# wireless_thermometer.net
KiCad netlist of a schematic drawn in EAGLE
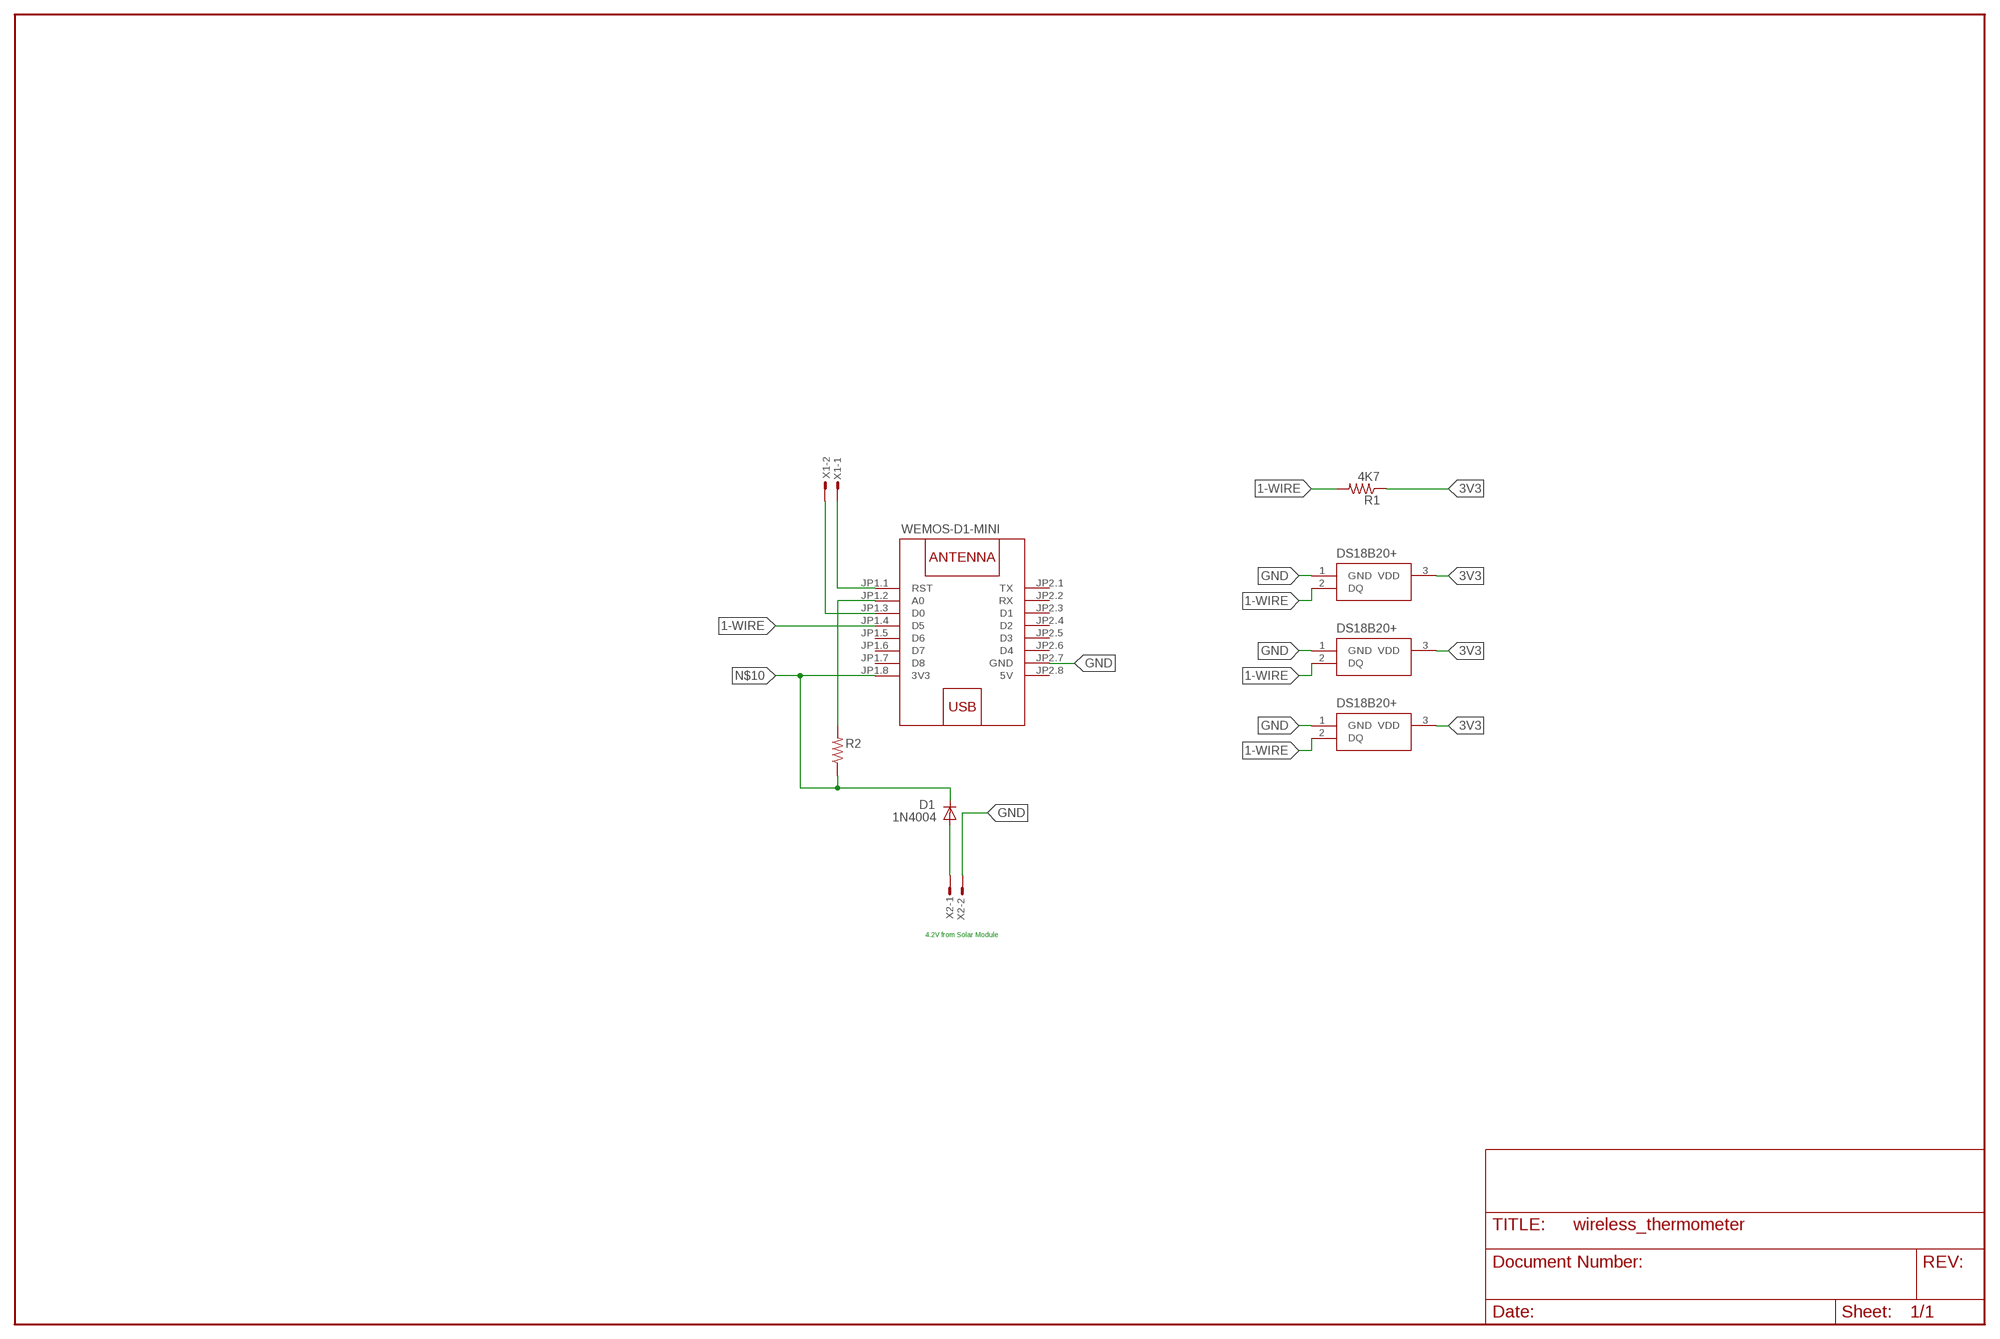
[diagram p0: schematic, sheet 1]

(export (version "E")
  (design (tool "Eeschema 10.0.6"))
  (components
    (comp (ref "D1")
      (value "1N4004")
      (footprint "eagle-import:DO41-10")
      (libsource (lib "eagle-import") (part "1N4004"))
    )
    (comp (ref "IC1")
      (value "DS18B20+")
      (footprint "eagle-import:TO-92")
      (fields (field (name "MOUSER_PART_NUMBER") "700-DS18B20+"))
      (libsource (lib "eagle-import") (part "DS18B20+"))
    )
    (comp (ref "IC2")
      (value "DS18B20+")
      (footprint "eagle-import:TO-92")
      (fields (field (name "MOUSER_PART_NUMBER") "700-DS18B20+"))
      (libsource (lib "eagle-import") (part "DS18B20+"))
    )
    (comp (ref "IC3")
      (value "DS18B20+")
      (footprint "eagle-import:TO-92")
      (fields (field (name "MOUSER_PART_NUMBER") "700-DS18B20+"))
      (libsource (lib "eagle-import") (part "DS18B20+"))
    )
    (comp (ref "R1")
      (value "4K7")
      (footprint "eagle-import:0207_10")
      (libsource (lib "eagle-import") (part "R-US_0207/10"))
    )
    (comp (ref "R2")
      (value "R-US_0204/7")
      (footprint "eagle-import:0204_7")
      (libsource (lib "eagle-import") (part "R-US_0204/7"))
    )
    (comp (ref "W1")
      (value "WEMOS-D1-MINI")
      (footprint "eagle-import:WEMOS-D1-MINI")
      (libsource (lib "eagle-import") (part "WEMOS-D1-MINI"))
    )
    (comp (ref "X1")
      (value "C-GRID-02-70543")
      (footprint "eagle-import:70543-02")
      (fields (field (name "MF") "MOLEX"))
      (libsource (lib "eagle-import") (part "C-GRID-02-70543"))
    )
    (comp (ref "X2")
      (value "C-GRID-02-70543")
      (footprint "eagle-import:70543-02")
      (fields (field (name "MF") "MOLEX"))
      (libsource (lib "eagle-import") (part "C-GRID-02-70543"))
    )
  )
  (nets
    (net (code "1") (name "/5V") (class "Default")
      (node (ref "W1") (pin "JP2.8") (pinfunction "5V_JP2.8") (pintype "power_in"))
    )
    (net (code "2") (name "1-WIRE") (class "Default")
      (node (ref "IC1") (pin "2") (pinfunction "DQ_2") (pintype "bidirectional"))
      (node (ref "IC2") (pin "2") (pinfunction "DQ_2") (pintype "bidirectional"))
      (node (ref "IC3") (pin "2") (pinfunction "DQ_2") (pintype "bidirectional"))
    )
    (net (code "3") (name "3V3") (class "Default")
      (node (ref "IC1") (pin "3") (pinfunction "VDD_3") (pintype "power_in"))
      (node (ref "IC2") (pin "3") (pinfunction "VDD_3") (pintype "power_in"))
    )
    (net (code "4") (name "GND") (class "Default")
      (node (ref "IC1") (pin "1") (pinfunction "GND_1") (pintype "power_in"))
      (node (ref "IC2") (pin "1") (pinfunction "GND_1") (pintype "power_in"))
      (node (ref "IC3") (pin "1") (pinfunction "GND_1") (pintype "power_in"))
      (node (ref "W1") (pin "JP2.7") (pinfunction "GND_JP2.7") (pintype "power_in"))
    )
    (net (code "5") (name "N$10") (class "Default")
      (node (ref "D1") (pin "C") (pinfunction "C_C") (pintype "passive"))
      (node (ref "R2") (pin "1") (pinfunction "1_1") (pintype "passive"))
      (node (ref "W1") (pin "JP1.8") (pinfunction "3V3_JP1.8") (pintype "power_in"))
    )
    (net (code "6") (name "Net-(W1-A0)") (class "Default")
      (node (ref "R2") (pin "2") (pinfunction "2_2") (pintype "passive"))
      (node (ref "W1") (pin "JP1.2") (pinfunction "A0_JP1.2") (pintype "bidirectional"))
    )
    (net (code "7") (name "Net-(W1-D0)") (class "Default")
      (node (ref "W1") (pin "JP1.3") (pinfunction "D0_JP1.3") (pintype "bidirectional"))
      (node (ref "X1") (pin "2") (pinfunction "S_2") (pintype "passive"))
    )
    (net (code "8") (name "Net-(W1-RST)") (class "Default")
      (node (ref "W1") (pin "JP1.1") (pinfunction "RST_JP1.1") (pintype "bidirectional"))
      (node (ref "X1") (pin "1") (pinfunction "S_1") (pintype "passive"))
    )
    (net (code "9") (name "Net-(X2A-S)") (class "Default")
      (node (ref "D1") (pin "A") (pinfunction "A_A") (pintype "passive"))
      (node (ref "X2") (pin "1") (pinfunction "S_1") (pintype "passive"))
    )
    (net (code "10") (name "unconnected-(IC3-VDD-Pad3)") (class "Default")
      (node (ref "IC3") (pin "3") (pinfunction "VDD_3") (pintype "power_in"))
    )
    (net (code "11") (name "unconnected-(R1-Pad1)") (class "Default")
      (node (ref "R1") (pin "1") (pinfunction "1_1") (pintype "passive"))
    )
    (net (code "12") (name "unconnected-(R1-Pad2)") (class "Default")
      (node (ref "R1") (pin "2") (pinfunction "2_2") (pintype "passive"))
    )
    (net (code "13") (name "unconnected-(W1-D1-PadJP2.3)") (class "Default")
      (node (ref "W1") (pin "JP2.3") (pinfunction "D1_JP2.3") (pintype "bidirectional"))
    )
    (net (code "14") (name "unconnected-(W1-D2-PadJP2.4)") (class "Default")
      (node (ref "W1") (pin "JP2.4") (pinfunction "D2_JP2.4") (pintype "bidirectional"))
    )
    (net (code "15") (name "unconnected-(W1-D3-PadJP2.5)") (class "Default")
      (node (ref "W1") (pin "JP2.5") (pinfunction "D3_JP2.5") (pintype "bidirectional"))
    )
    (net (code "16") (name "unconnected-(W1-D4-PadJP2.6)") (class "Default")
      (node (ref "W1") (pin "JP2.6") (pinfunction "D4_JP2.6") (pintype "bidirectional"))
    )
    (net (code "17") (name "unconnected-(W1-D5-PadJP1.4)") (class "Default")
      (node (ref "W1") (pin "JP1.4") (pinfunction "D5_JP1.4") (pintype "bidirectional"))
    )
    (net (code "18") (name "unconnected-(W1-D6-PadJP1.5)") (class "Default")
      (node (ref "W1") (pin "JP1.5") (pinfunction "D6_JP1.5") (pintype "bidirectional"))
    )
    (net (code "19") (name "unconnected-(W1-D7-PadJP1.6)") (class "Default")
      (node (ref "W1") (pin "JP1.6") (pinfunction "D7_JP1.6") (pintype "bidirectional"))
    )
    (net (code "20") (name "unconnected-(W1-D8-PadJP1.7)") (class "Default")
      (node (ref "W1") (pin "JP1.7") (pinfunction "D8_JP1.7") (pintype "bidirectional"))
    )
    (net (code "21") (name "unconnected-(W1-RX-PadJP2.2)") (class "Default")
      (node (ref "W1") (pin "JP2.2") (pinfunction "RX_JP2.2") (pintype "bidirectional"))
    )
    (net (code "22") (name "unconnected-(W1-TX-PadJP2.1)") (class "Default")
      (node (ref "W1") (pin "JP2.1") (pinfunction "TX_JP2.1") (pintype "bidirectional"))
    )
    (net (code "23") (name "unconnected-(X2B-S-Pad2)") (class "Default")
      (node (ref "X2") (pin "2") (pinfunction "S_2") (pintype "passive"))
    )
  )
)
